# Noduino-Open-Plug.net
KiCad netlist of a schematic drawn in EAGLE
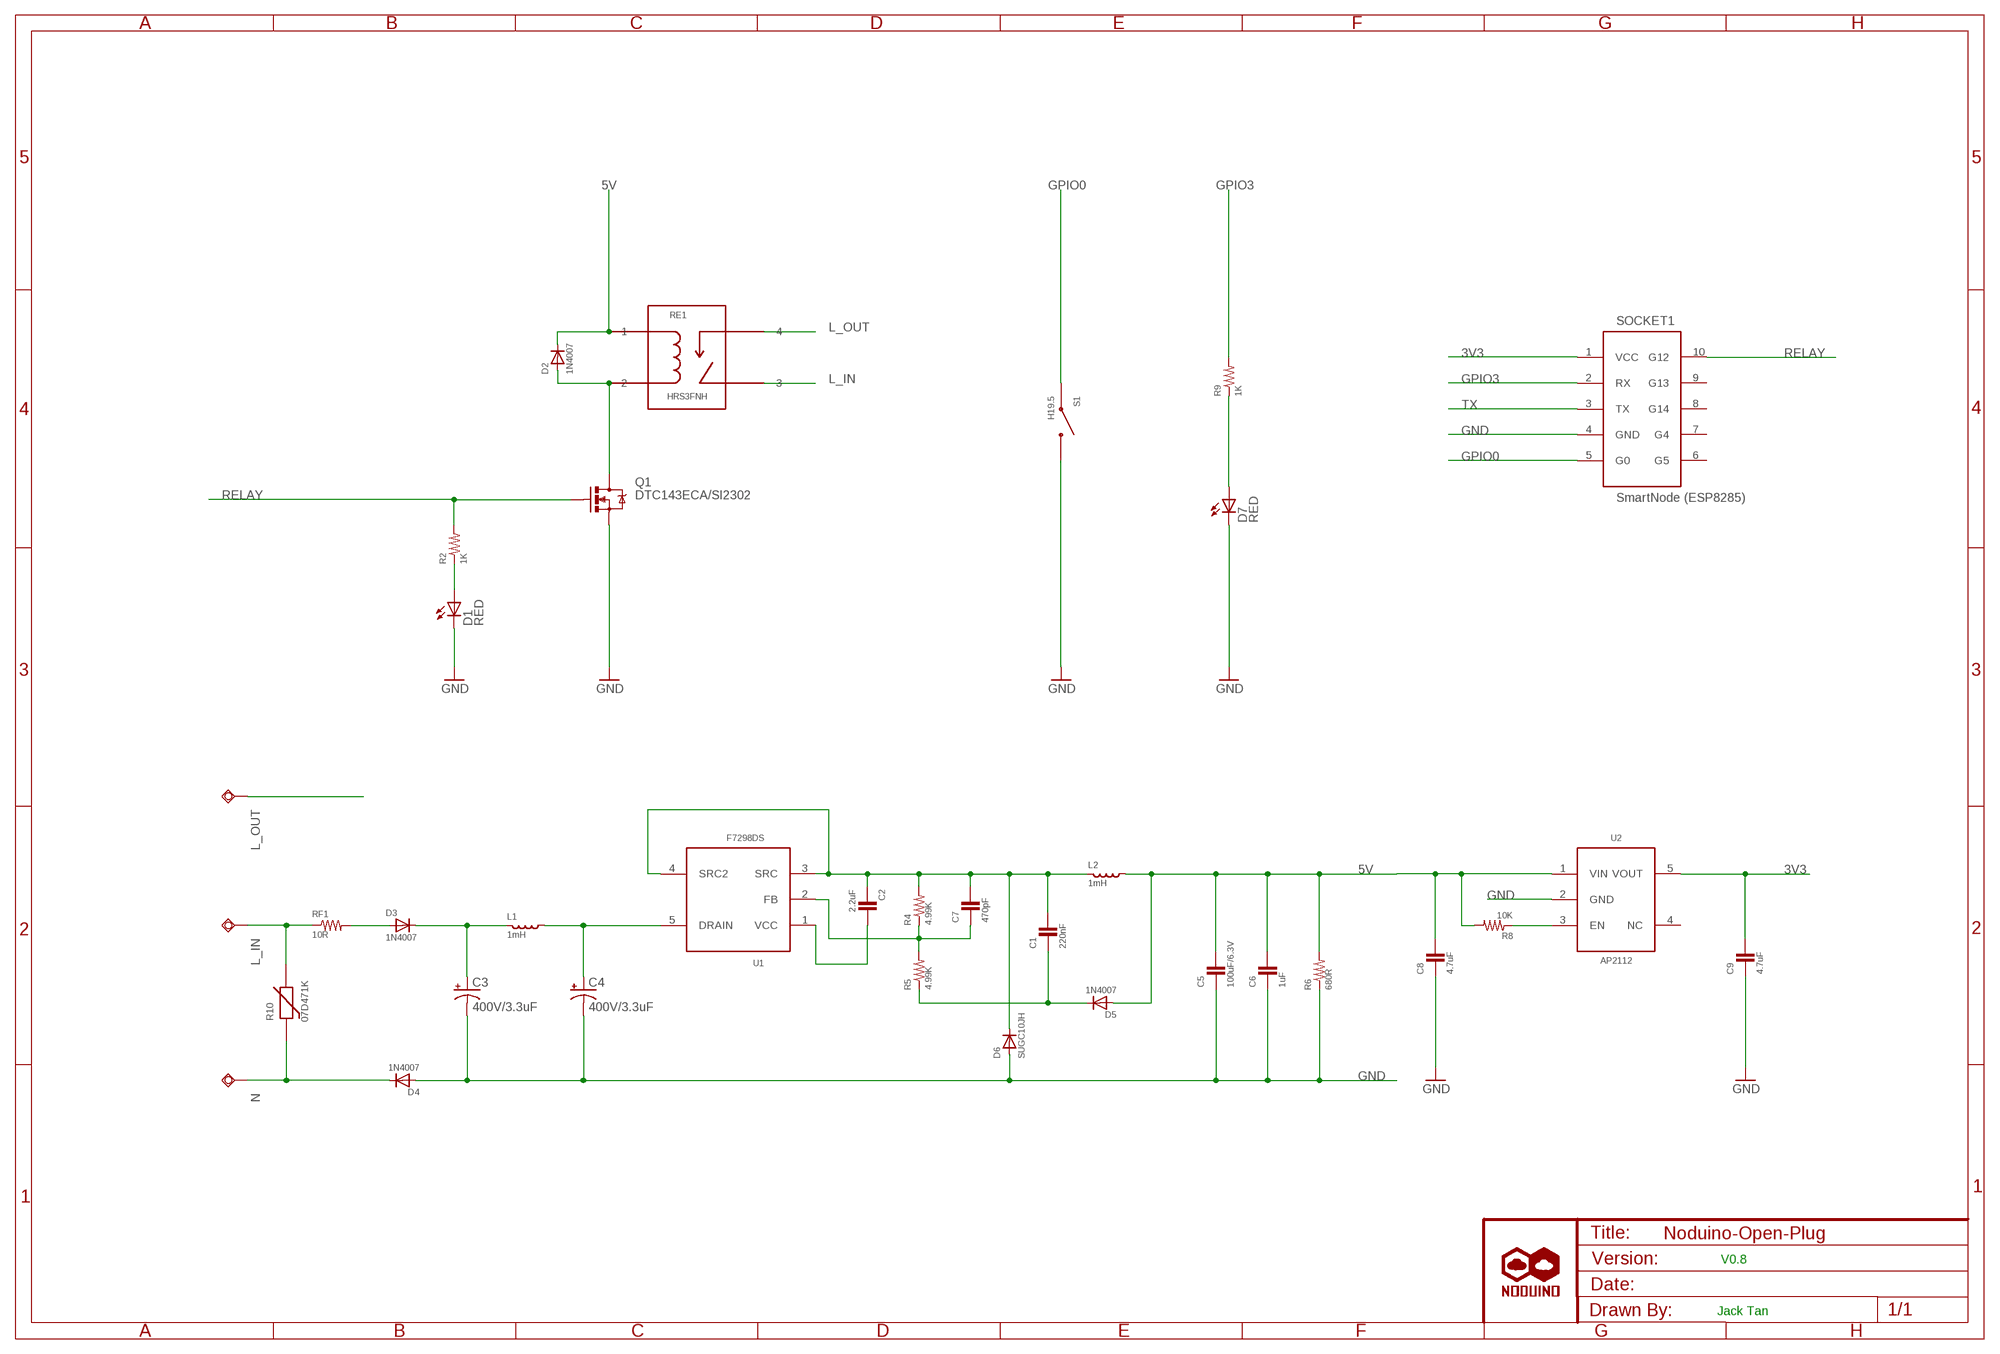
[diagram p0: schematic, sheet 1]

(export (version "E")
  (design (tool "Eeschema 10.0.6"))
  (components
    (comp (ref "C1")
      (value "220nF")
      (footprint "eagle-import:0402-CAP")
      (libsource (lib "eagle-import") (part "0402-CAP"))
    )
    (comp (ref "C2")
      (value "2.2uF")
      (footprint "eagle-import:0603-CAP")
      (libsource (lib "eagle-import") (part "0603-CAP"))
    )
    (comp (ref "C3")
      (value "400V/3.3uF")
      (footprint "eagle-import:CPOL-RADIOA-3.3UF-400V")
      (libsource (lib "eagle-import") (part "CAP_POL"))
    )
    (comp (ref "C4")
      (value "400V/3.3uF")
      (footprint "eagle-import:CPOL-RADIOA-3.3UF-400V")
      (libsource (lib "eagle-import") (part "CAP_POL"))
    )
    (comp (ref "C5")
      (value "100uF/6.3V")
      (footprint "eagle-import:B3528-CAP")
      (libsource (lib "eagle-import") (part "B3528-CAP"))
    )
    (comp (ref "C6")
      (value "1uF")
      (footprint "eagle-import:0402-CAP")
      (libsource (lib "eagle-import") (part "0402-CAP"))
    )
    (comp (ref "C7")
      (value "470pF")
      (footprint "eagle-import:0402-CAP")
      (libsource (lib "eagle-import") (part "0402-CAP"))
    )
    (comp (ref "C8")
      (value "4.7uF")
      (footprint "eagle-import:0603-CAP")
      (libsource (lib "eagle-import") (part "0603-CAP"))
    )
    (comp (ref "C9")
      (value "4.7uF")
      (footprint "eagle-import:0603-CAP")
      (libsource (lib "eagle-import") (part "0603-CAP"))
    )
    (comp (ref "D1")
      (value "RED")
      (footprint "eagle-import:LED3MM")
      (libsource (lib "eagle-import") (part "LED3MM"))
    )
    (comp (ref "D2")
      (value "1N4007")
      (footprint "eagle-import:SOD-323")
      (libsource (lib "eagle-import") (part "DIODESOD"))
    )
    (comp (ref "D3")
      (value "1N4007")
      (footprint "eagle-import:DO-214")
      (libsource (lib "eagle-import") (part "DIODEHV"))
    )
    (comp (ref "D4")
      (value "1N4007")
      (footprint "eagle-import:DO-214")
      (libsource (lib "eagle-import") (part "DIODEHV"))
    )
    (comp (ref "D5")
      (value "1N4007")
      (footprint "eagle-import:DO-214")
      (libsource (lib "eagle-import") (part "DIODEHV"))
    )
    (comp (ref "D6")
      (value "SUGC10JH")
      (footprint "eagle-import:SOD-123")
      (libsource (lib "eagle-import") (part "SUGC10JH"))
    )
    (comp (ref "D7")
      (value "RED")
      (footprint "eagle-import:LED3MM")
      (libsource (lib "eagle-import") (part "LED3MM"))
    )
    (comp (ref "L1")
      (value "1mH")
      (footprint "eagle-import:3-0.5-5")
      (libsource (lib "eagle-import") (part "INDUCTOR3-0.5-5"))
    )
    (comp (ref "L2")
      (value "1mH")
      (footprint "eagle-import:INDUCTOR-5-0.5")
      (libsource (lib "eagle-import") (part "INDUCTOR"))
    )
    (comp (ref "L_IN")
      (value "TESTPAD50/25")
      (footprint "eagle-import:1SMD")
      (libsource (lib "eagle-import") (part "TESTPAD50/25"))
    )
    (comp (ref "L_OUT")
      (value "TESTPAD50/25")
      (footprint "eagle-import:1SMD")
      (libsource (lib "eagle-import") (part "TESTPAD50/25"))
    )
    (comp (ref "N")
      (value "TESTPAD50/25")
      (footprint "eagle-import:1SMD")
      (libsource (lib "eagle-import") (part "TESTPAD50/25"))
    )
    (comp (ref "Q1")
      (value "DTC143ECA/SI2302")
      (footprint "eagle-import:SOT23-3")
      (libsource (lib "eagle-import") (part "MOSFET-N-SMD"))
    )
    (comp (ref "R2")
      (value "1K")
      (footprint "eagle-import:0603-RES")
      (libsource (lib "eagle-import") (part "0603-RESISTOR"))
    )
    (comp (ref "R4")
      (value "4.99K")
      (footprint "eagle-import:0402-RES")
      (libsource (lib "eagle-import") (part "0402-RESISTOR"))
    )
    (comp (ref "R5")
      (value "4.99K")
      (footprint "eagle-import:0402-RES")
      (libsource (lib "eagle-import") (part "0402-RESISTOR"))
    )
    (comp (ref "R6")
      (value "680R")
      (footprint "eagle-import:0402-RES")
      (libsource (lib "eagle-import") (part "0402-RESISTOR"))
    )
    (comp (ref "R8")
      (value "10K")
      (footprint "eagle-import:0603-RES")
      (libsource (lib "eagle-import") (part "0603-RESISTOR"))
    )
    (comp (ref "R9")
      (value "1K")
      (footprint "eagle-import:0603-RES")
      (libsource (lib "eagle-import") (part "0603-RESISTOR"))
    )
    (comp (ref "R10")
      (value "07D471K")
      (footprint "eagle-import:07D471K")
      (libsource (lib "eagle-import") (part "07D471K"))
    )
    (comp (ref "RE1")
      (value "HRS3FNH")
      (footprint "eagle-import:HKE-HRS3FN")
      (libsource (lib "eagle-import") (part "HKE-HRS3FNH"))
    )
    (comp (ref "RF1")
      (value "10R")
      (footprint "eagle-import:3-0.5-5")
      (libsource (lib "eagle-import") (part "RESISTOR"))
    )
    (comp (ref "S1")
      (value "H19.5")
      (footprint "eagle-import:SWITCH-TS-037-PLUG")
      (libsource (lib "eagle-import") (part "SWITCH-4DIPTS-037-PLUG"))
    )
    (comp (ref "SOCKET1")
      (value "SmartNode (ESP8285)")
      (footprint "eagle-import:MOD-PLUG-SOCKET")
      (libsource (lib "eagle-import") (part "MOD-PLUG-SOCKET"))
    )
    (comp (ref "U$1")
      (value "NODUINO-LOGO-ALL")
      (footprint "eagle-import:NODUINO-ALL-1")
      (libsource (lib "eagle-import") (part "NODUINO-LOGO-ALL"))
    )
    (comp (ref "U1")
      (value "F7298")
      (footprint "eagle-import:SOT23-5")
      (libsource (lib "eagle-import") (part "F7298"))
    )
    (comp (ref "U2")
      (value "AP2112")
      (footprint "eagle-import:SOT23-5")
      (libsource (lib "eagle-import") (part "AP2112"))
    )
  )
  (nets
    (net (code "1") (name "/3V3") (class "Default")
      (node (ref "C9") (pin "2") (pinfunction "2_2") (pintype "passive"))
      (node (ref "SOCKET1") (pin "1") (pinfunction "VCC_1") (pintype "bidirectional"))
      (node (ref "U2") (pin "5") (pinfunction "VOUT_5") (pintype "bidirectional"))
    )
    (net (code "2") (name "/5V") (class "Default")
      (node (ref "C5") (pin "2") (pinfunction "2_2") (pintype "passive"))
      (node (ref "C6") (pin "2") (pinfunction "2_2") (pintype "passive"))
      (node (ref "C8") (pin "2") (pinfunction "2_2") (pintype "passive"))
      (node (ref "D2") (pin "1") (pinfunction "C_1") (pintype "passive"))
      (node (ref "D5") (pin "A") (pinfunction "A_A") (pintype "passive"))
      (node (ref "L2") (pin "P$2") (pinfunction "X2_P$2") (pintype "bidirectional"))
      (node (ref "R6") (pin "2") (pinfunction "2_2") (pintype "passive"))
      (node (ref "R8") (pin "2") (pinfunction "2_2") (pintype "passive"))
      (node (ref "RE1") (pin "1") (pinfunction "1_1") (pintype "bidirectional"))
      (node (ref "U2") (pin "1") (pinfunction "VIN_1") (pintype "bidirectional"))
    )
    (net (code "3") (name "/GPIO0") (class "Default")
      (node (ref "S1") (pin "P$3") (pinfunction "2_P$3") (pintype "bidirectional"))
      (node (ref "SOCKET1") (pin "5") (pinfunction "G0_5") (pintype "bidirectional"))
    )
    (net (code "4") (name "/GPIO3") (class "Default")
      (node (ref "R9") (pin "2") (pinfunction "2_2") (pintype "passive"))
      (node (ref "SOCKET1") (pin "2") (pinfunction "RX_2") (pintype "bidirectional"))
    )
    (net (code "5") (name "/L_IN") (class "Default")
      (node (ref "L_IN") (pin "1") (pinfunction "PP_1") (pintype "passive"))
      (node (ref "R10") (pin "P$2") (pinfunction "2_P$2") (pintype "passive"))
      (node (ref "RE1") (pin "3") (pinfunction "3_3") (pintype "bidirectional"))
      (node (ref "RF1") (pin "P$1") (pinfunction "1_P$1") (pintype "passive"))
    )
    (net (code "6") (name "/L_OUT") (class "Default")
      (node (ref "L_OUT") (pin "1") (pinfunction "PP_1") (pintype "passive"))
      (node (ref "RE1") (pin "4") (pinfunction "4_4") (pintype "bidirectional"))
    )
    (net (code "7") (name "/RELAY") (class "Default")
      (node (ref "Q1") (pin "1") (pinfunction "G_1") (pintype "passive"))
      (node (ref "R2") (pin "2") (pinfunction "2_2") (pintype "passive"))
      (node (ref "SOCKET1") (pin "10") (pinfunction "G12_10") (pintype "bidirectional"))
    )
    (net (code "8") (name "/TX") (class "Default")
      (node (ref "SOCKET1") (pin "3") (pinfunction "TX_3") (pintype "bidirectional"))
    )
    (net (code "9") (name "GND") (class "Default")
      (node (ref "C3") (pin "P$2") (pinfunction "-_P$2") (pintype "passive"))
      (node (ref "C4") (pin "P$2") (pinfunction "-_P$2") (pintype "passive"))
      (node (ref "C5") (pin "1") (pinfunction "1_1") (pintype "passive"))
      (node (ref "C6") (pin "1") (pinfunction "1_1") (pintype "passive"))
      (node (ref "C8") (pin "1") (pinfunction "1_1") (pintype "passive"))
      (node (ref "C9") (pin "1") (pinfunction "1_1") (pintype "passive"))
      (node (ref "D1") (pin "K") (pinfunction "C_K") (pintype "passive"))
      (node (ref "D4") (pin "A") (pinfunction "A_A") (pintype "passive"))
      (node (ref "D6") (pin "A") (pinfunction "A_A") (pintype "passive"))
      (node (ref "D7") (pin "K") (pinfunction "C_K") (pintype "passive"))
      (node (ref "Q1") (pin "2") (pinfunction "S_2") (pintype "passive"))
      (node (ref "R6") (pin "1") (pinfunction "1_1") (pintype "passive"))
      (node (ref "S1") (pin "P$1") (pinfunction "1_P$1") (pintype "bidirectional"))
      (node (ref "SOCKET1") (pin "4") (pinfunction "GND_4") (pintype "bidirectional"))
      (node (ref "U2") (pin "2") (pinfunction "GND_2") (pintype "bidirectional"))
    )
    (net (code "10") (name "Net-(C1-Pad1)") (class "Default")
      (node (ref "C1") (pin "1") (pinfunction "1_1") (pintype "passive"))
      (node (ref "D5") (pin "C") (pinfunction "C_C") (pintype "passive"))
      (node (ref "R5") (pin "1") (pinfunction "1_1") (pintype "passive"))
    )
    (net (code "11") (name "Net-(C3-+)") (class "Default")
      (node (ref "C3") (pin "P$1") (pinfunction "+_P$1") (pintype "passive"))
      (node (ref "D3") (pin "C") (pinfunction "C_C") (pintype "passive"))
      (node (ref "L1") (pin "P$1") (pinfunction "X1_P$1") (pintype "bidirectional"))
    )
    (net (code "12") (name "Net-(C4-+)") (class "Default")
      (node (ref "C4") (pin "P$1") (pinfunction "+_P$1") (pintype "passive"))
      (node (ref "L1") (pin "P$2") (pinfunction "X2_P$2") (pintype "bidirectional"))
      (node (ref "U1") (pin "5") (pinfunction "DRAIN_5") (pintype "bidirectional"))
    )
    (net (code "13") (name "Net-(D1-PadA)") (class "Default")
      (node (ref "D1") (pin "A") (pinfunction "A_A") (pintype "passive"))
      (node (ref "R2") (pin "1") (pinfunction "1_1") (pintype "passive"))
    )
    (net (code "14") (name "Net-(D2-A)") (class "Default")
      (node (ref "D2") (pin "2") (pinfunction "A_2") (pintype "passive"))
      (node (ref "Q1") (pin "3") (pinfunction "D_3") (pintype "passive"))
      (node (ref "RE1") (pin "2") (pinfunction "2_2") (pintype "bidirectional"))
    )
    (net (code "15") (name "Net-(D7-PadA)") (class "Default")
      (node (ref "D7") (pin "A") (pinfunction "A_A") (pintype "passive"))
      (node (ref "R9") (pin "1") (pinfunction "1_1") (pintype "passive"))
    )
    (net (code "16") (name "Net-(L2-X1)") (class "Default")
      (node (ref "C1") (pin "2") (pinfunction "2_2") (pintype "passive"))
      (node (ref "C2") (pin "1") (pinfunction "1_1") (pintype "passive"))
      (node (ref "C7") (pin "2") (pinfunction "2_2") (pintype "passive"))
      (node (ref "D6") (pin "C") (pinfunction "C_C") (pintype "passive"))
      (node (ref "L2") (pin "P$1") (pinfunction "X1_P$1") (pintype "bidirectional"))
      (node (ref "R4") (pin "2") (pinfunction "2_2") (pintype "passive"))
      (node (ref "U1") (pin "3") (pinfunction "SRC_3") (pintype "bidirectional"))
      (node (ref "U1") (pin "4") (pinfunction "SRC2_4") (pintype "bidirectional"))
    )
    (net (code "17") (name "Net-(N-PP)") (class "Default")
      (node (ref "D4") (pin "C") (pinfunction "C_C") (pintype "passive"))
      (node (ref "N") (pin "1") (pinfunction "PP_1") (pintype "passive"))
      (node (ref "R10") (pin "P$1") (pinfunction "1_P$1") (pintype "passive"))
    )
    (net (code "18") (name "Net-(RF1-2)") (class "Default")
      (node (ref "D3") (pin "A") (pinfunction "A_A") (pintype "passive"))
      (node (ref "RF1") (pin "P$2") (pinfunction "2_P$2") (pintype "passive"))
    )
    (net (code "19") (name "Net-(U1-FB)") (class "Default")
      (node (ref "C7") (pin "1") (pinfunction "1_1") (pintype "passive"))
      (node (ref "R4") (pin "1") (pinfunction "1_1") (pintype "passive"))
      (node (ref "R5") (pin "2") (pinfunction "2_2") (pintype "passive"))
      (node (ref "U1") (pin "2") (pinfunction "FB_2") (pintype "bidirectional"))
    )
    (net (code "20") (name "Net-(U1-VCC)") (class "Default")
      (node (ref "C2") (pin "2") (pinfunction "2_2") (pintype "passive"))
      (node (ref "U1") (pin "1") (pinfunction "VCC_1") (pintype "bidirectional"))
    )
    (net (code "21") (name "Net-(U2-EN)") (class "Default")
      (node (ref "R8") (pin "1") (pinfunction "1_1") (pintype "passive"))
      (node (ref "U2") (pin "3") (pinfunction "EN_3") (pintype "bidirectional"))
    )
    (net (code "22") (name "unconnected-(SOCKET1-G4-Pad7)") (class "Default")
      (node (ref "SOCKET1") (pin "7") (pinfunction "G4_7") (pintype "bidirectional"))
    )
    (net (code "23") (name "unconnected-(SOCKET1-G5-Pad6)") (class "Default")
      (node (ref "SOCKET1") (pin "6") (pinfunction "G5_6") (pintype "bidirectional"))
    )
    (net (code "24") (name "unconnected-(SOCKET1-G13-Pad9)") (class "Default")
      (node (ref "SOCKET1") (pin "9") (pinfunction "G13_9") (pintype "bidirectional"))
    )
    (net (code "25") (name "unconnected-(SOCKET1-G14-Pad8)") (class "Default")
      (node (ref "SOCKET1") (pin "8") (pinfunction "G14_8") (pintype "bidirectional"))
    )
    (net (code "26") (name "unconnected-(U2-NC-Pad4)") (class "Default")
      (node (ref "U2") (pin "4") (pinfunction "NC_4") (pintype "bidirectional"))
    )
  )
)
